# LM317.net
KiCad netlist of a schematic drawn in Altium Designer
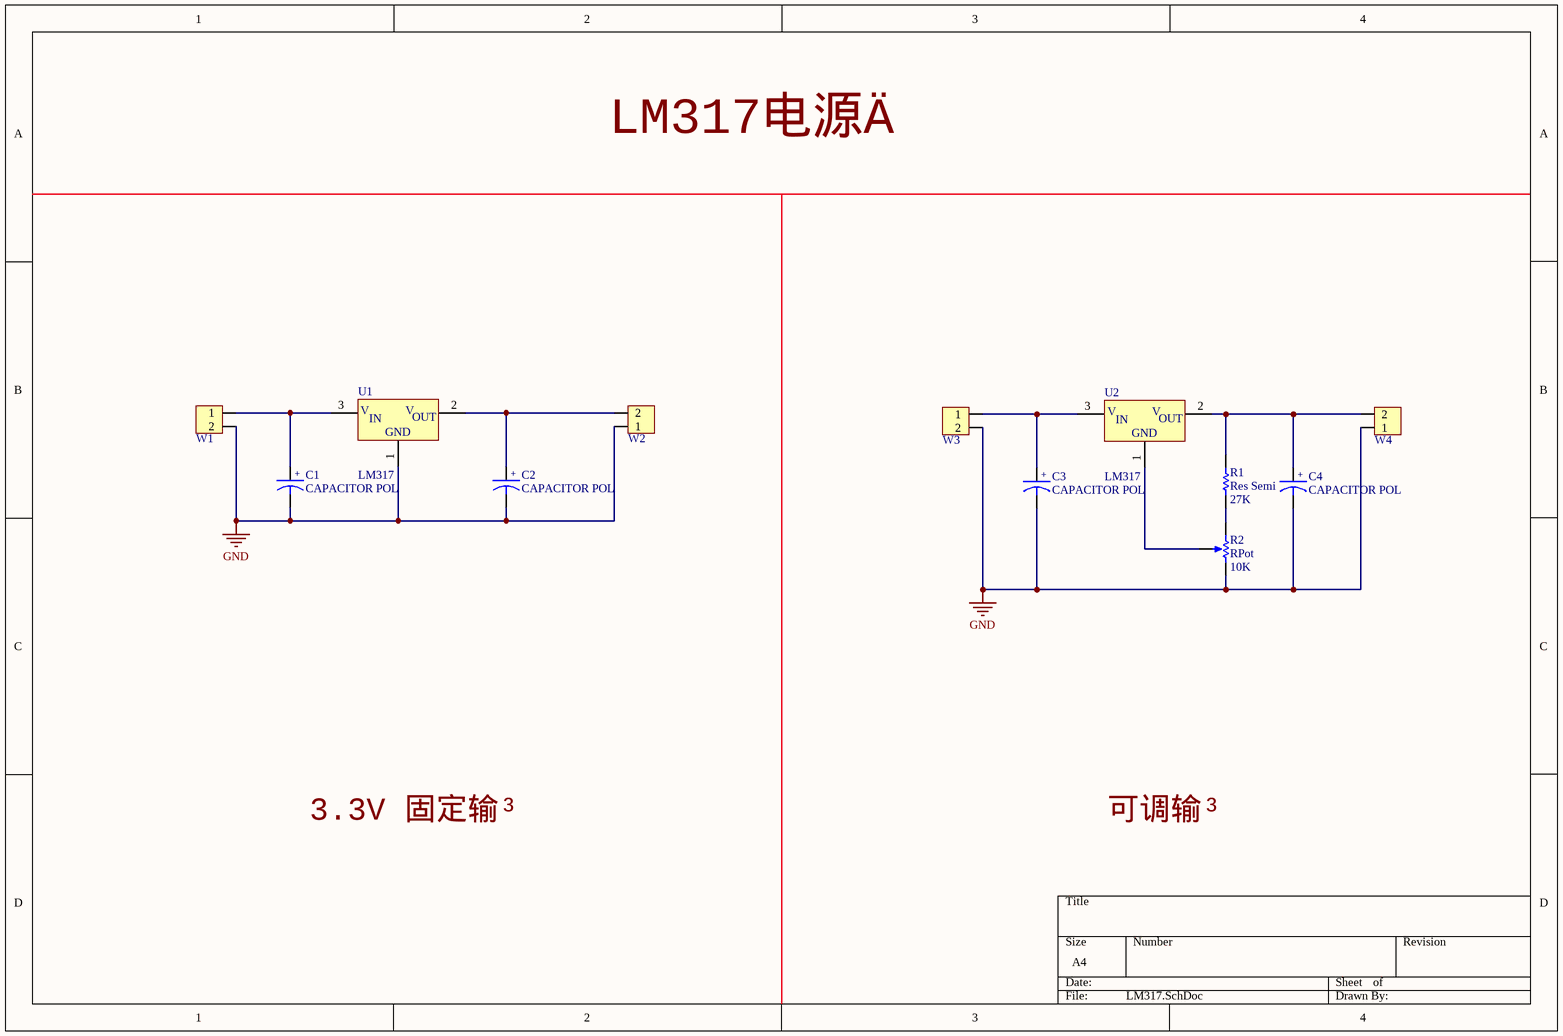
[diagram p0: LM317.SchDoc]

(export (version "E")
  (design (tool "Eeschema 10.0.6"))
  (components
    (comp (ref "C1")
      (value "CAPACITOR POL")
      (footprint "Cap_Pol_F5")
      (description "Capacitor")
      (libsource (lib "My_Integrated_Library") (part "CAPACITOR POL"))
    )
    (comp (ref "C2")
      (value "CAPACITOR POL")
      (footprint "Cap_Pol_F6")
      (description "Capacitor")
      (libsource (lib "My_Integrated_Library") (part "CAPACITOR POL"))
    )
    (comp (ref "C3")
      (value "CAPACITOR POL")
      (footprint "Cap_Pol_F5")
      (description "10uF")
      (libsource (lib "My_Integrated_Library") (part "CAPACITOR POL"))
    )
    (comp (ref "C4")
      (value "CAPACITOR POL")
      (footprint "Cap_Pol_F6")
      (description "Capacitor")
      (libsource (lib "My_Integrated_Library") (part "CAPACITOR POL"))
    )
    (comp (ref "R1")
      (value "Res Semi")
      (footprint "AXIAL-0.5")
      (description "Semiconductor Resistor")
      (fields (field (name "ALTIUM_VALUE") "27K") (field (name "PUBLISHER") "Altium Limited"))
      (libsource (lib "Miscellaneous Devices") (part "Res Semi"))
    )
    (comp (ref "R2")
      (value "RPot")
      (footprint "VR5")
      (description "Potentiometer")
      (fields (field (name "ALTIUM_VALUE") "10K") (field (name "PUBLISHER") "Altium Limited"))
      (libsource (lib "Miscellaneous Devices") (part "RPot"))
    )
    (comp (ref "U1")
      (value "LM317")
      (footprint "78XX")
      (description "LM317 电源芯片")
      (libsource (lib "My_Integrated_Library") (part "LM317"))
    )
    (comp (ref "U2")
      (value "LM317")
      (footprint "78XX")
      (description "LM317 电源芯片")
      (libsource (lib "My_Integrated_Library") (part "LM317"))
    )
    (comp (ref "W1")
      (value "2Way_5")
      (footprint "2Way_5")
      (description "DB")
      (libsource (lib "My_Integrated_Library") (part "2Way_5"))
    )
    (comp (ref "W2")
      (value "2Way_5")
      (footprint "2Way_5")
      (description "DB")
      (libsource (lib "") (part "2Way_5_1"))
    )
    (comp (ref "W3")
      (value "2Way_5")
      (footprint "2Way_5")
      (description "DB")
      (libsource (lib "My_Integrated_Library") (part "2Way_5"))
    )
    (comp (ref "W4")
      (value "2Way_5")
      (footprint "2Way_5")
      (description "DB")
      (libsource (lib "") (part "2Way_5_1"))
    )
  )
  (nets
    (net (code "1") (name "GND") (class "Default")
      (node (ref "C1") (pin "2") (pinfunction "2_2") (pintype "passive"))
      (node (ref "C2") (pin "2") (pinfunction "2_2") (pintype "passive"))
      (node (ref "C3") (pin "2") (pinfunction "2_2") (pintype "passive"))
      (node (ref "C4") (pin "2") (pinfunction "2_2") (pintype "passive"))
      (node (ref "R2") (pin "2") (pinfunction "BOT_2") (pintype "passive"))
      (node (ref "U1") (pin "1") (pinfunction "GND_1") (pintype "passive"))
      (node (ref "W1") (pin "2") (pinfunction "2_2") (pintype "passive"))
      (node (ref "W2") (pin "1") (pinfunction "1_1") (pintype "passive"))
      (node (ref "W3") (pin "2") (pinfunction "2_2") (pintype "passive"))
      (node (ref "W4") (pin "1") (pinfunction "1_1") (pintype "passive"))
    )
    (net (code "2") (name "Net-(R2-TAP)") (class "Default")
      (node (ref "R2") (pin "3") (pinfunction "TAP_3") (pintype "passive"))
      (node (ref "U2") (pin "1") (pinfunction "GND_1") (pintype "passive"))
    )
    (net (code "3") (name "Net-(R2-TOP)") (class "Default")
      (node (ref "R1") (pin "2") (pinfunction "2_2") (pintype "passive"))
      (node (ref "R2") (pin "1") (pinfunction "TOP_1") (pintype "passive"))
    )
    (net (code "4") (name "Net-(U1-VIN)") (class "Default")
      (node (ref "C1") (pin "1") (pinfunction "1_1") (pintype "passive"))
      (node (ref "U1") (pin "3") (pinfunction "VIN_3") (pintype "passive"))
      (node (ref "W1") (pin "1") (pinfunction "1_1") (pintype "passive"))
    )
    (net (code "5") (name "Net-(U1-VOUT)") (class "Default")
      (node (ref "C2") (pin "1") (pinfunction "1_1") (pintype "passive"))
      (node (ref "U1") (pin "2") (pinfunction "VOUT_2") (pintype "passive"))
      (node (ref "W2") (pin "2") (pinfunction "2_2") (pintype "passive"))
    )
    (net (code "6") (name "Net-(U2-VIN)") (class "Default")
      (node (ref "C3") (pin "1") (pinfunction "1_1") (pintype "passive"))
      (node (ref "U2") (pin "3") (pinfunction "VIN_3") (pintype "passive"))
      (node (ref "W3") (pin "1") (pinfunction "1_1") (pintype "passive"))
    )
    (net (code "7") (name "Net-(U2-VOUT)") (class "Default")
      (node (ref "C4") (pin "1") (pinfunction "1_1") (pintype "passive"))
      (node (ref "R1") (pin "1") (pinfunction "1_1") (pintype "passive"))
      (node (ref "U2") (pin "2") (pinfunction "VOUT_2") (pintype "passive"))
      (node (ref "W4") (pin "2") (pinfunction "2_2") (pintype "passive"))
    )
  )
)
